# iobuf.net
KiCad netlist of a schematic drawn in EAGLE
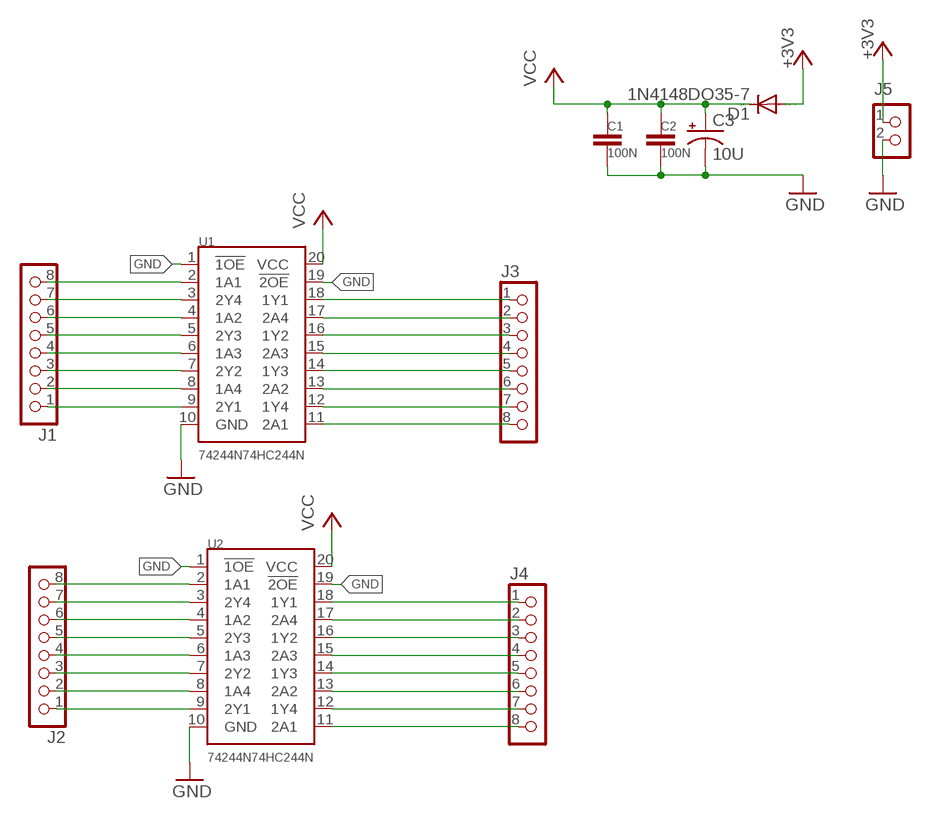
[diagram p0: schematic, sheet 1]

(export (version "E")
  (design (tool "Eeschema 10.0.6"))
  (components
    (comp (ref "C1")
      (value "100N")
      (footprint "eagle-import:C025-025X050")
      (libsource (lib "eagle-import") (part "C-EU025-025X050"))
    )
    (comp (ref "C2")
      (value "100N")
      (footprint "eagle-import:C025-025X050")
      (libsource (lib "eagle-import") (part "C-EU025-025X050"))
    )
    (comp (ref "C3")
      (value "10U")
      (footprint "eagle-import:E2,5-7")
      (libsource (lib "eagle-import") (part "CPOL-USE2.5-7"))
    )
    (comp (ref "D1")
      (value "1N4148DO35-7")
      (footprint "eagle-import:DO35-7")
      (libsource (lib "eagle-import") (part "1N4148DO35-7"))
    )
    (comp (ref "J1")
      (value "CON_HEADER_1X08-PTH")
      (footprint "eagle-import:M1X8")
      (libsource (lib "eagle-import") (part "CON_HEADER_1X08-PTH"))
    )
    (comp (ref "J2")
      (value "CON_HEADER_1X08-PTH")
      (footprint "eagle-import:M1X8")
      (libsource (lib "eagle-import") (part "CON_HEADER_1X08-PTH"))
    )
    (comp (ref "J3")
      (value "CON_HEADER_1X08-PTH")
      (footprint "eagle-import:M1X8")
      (libsource (lib "eagle-import") (part "CON_HEADER_1X08-PTH"))
    )
    (comp (ref "J4")
      (value "CON_HEADER_1X08-PTH")
      (footprint "eagle-import:M1X8")
      (libsource (lib "eagle-import") (part "CON_HEADER_1X08-PTH"))
    )
    (comp (ref "J5")
      (value "CON_HEADER_1X02-PTH")
      (footprint "eagle-import:M1X2")
      (libsource (lib "eagle-import") (part "CON_HEADER_1X02-PTH"))
    )
    (comp (ref "U1")
      (value "74244N74HC244N")
      (footprint "eagle-import:DIL20")
      (libsource (lib "eagle-import") (part "74244N74HC244N"))
    )
    (comp (ref "U2")
      (value "74244N74HC244N")
      (footprint "eagle-import:DIL20")
      (libsource (lib "eagle-import") (part "74244N74HC244N"))
    )
  )
  (nets
    (net (code "1") (name "+3V3") (class "Default")
      (node (ref "D1") (pin "A") (pinfunction "A_A") (pintype "passive"))
      (node (ref "J5") (pin "1") (pinfunction "1_1") (pintype "passive"))
    )
    (net (code "2") (name "GND") (class "Default")
      (node (ref "C1") (pin "2") (pinfunction "2_2") (pintype "passive"))
      (node (ref "C2") (pin "2") (pinfunction "2_2") (pintype "passive"))
      (node (ref "C3") (pin "-") (pinfunction "-_-") (pintype "passive"))
      (node (ref "J5") (pin "2") (pinfunction "2_2") (pintype "passive"))
      (node (ref "U1") (pin "1") (pinfunction "~{1OE}_1") (pintype "input"))
      (node (ref "U1") (pin "10") (pinfunction "GND_10") (pintype "power_in"))
      (node (ref "U1") (pin "19") (pinfunction "~{2OE}_19") (pintype "input"))
      (node (ref "U2") (pin "1") (pinfunction "~{1OE}_1") (pintype "input"))
      (node (ref "U2") (pin "10") (pinfunction "GND_10") (pintype "power_in"))
      (node (ref "U2") (pin "19") (pinfunction "~{2OE}_19") (pintype "input"))
    )
    (net (code "3") (name "Net-(U1-1A1)") (class "Default")
      (node (ref "J1") (pin "8") (pinfunction "8_8") (pintype "passive"))
      (node (ref "U1") (pin "2") (pinfunction "1A1_2") (pintype "bidirectional"))
    )
    (net (code "4") (name "Net-(U1-1A2)") (class "Default")
      (node (ref "J1") (pin "6") (pinfunction "6_6") (pintype "passive"))
      (node (ref "U1") (pin "4") (pinfunction "1A2_4") (pintype "bidirectional"))
    )
    (net (code "5") (name "Net-(U1-1A3)") (class "Default")
      (node (ref "J1") (pin "4") (pinfunction "4_4") (pintype "passive"))
      (node (ref "U1") (pin "6") (pinfunction "1A3_6") (pintype "bidirectional"))
    )
    (net (code "6") (name "Net-(U1-1A4)") (class "Default")
      (node (ref "J1") (pin "2") (pinfunction "2_2") (pintype "passive"))
      (node (ref "U1") (pin "8") (pinfunction "1A4_8") (pintype "bidirectional"))
    )
    (net (code "7") (name "Net-(U1-1Y1)") (class "Default")
      (node (ref "J3") (pin "1") (pinfunction "1_1") (pintype "passive"))
      (node (ref "U1") (pin "18") (pinfunction "1Y1_18") (pintype "bidirectional"))
    )
    (net (code "8") (name "Net-(U1-1Y2)") (class "Default")
      (node (ref "J3") (pin "3") (pinfunction "3_3") (pintype "passive"))
      (node (ref "U1") (pin "16") (pinfunction "1Y2_16") (pintype "bidirectional"))
    )
    (net (code "9") (name "Net-(U1-1Y3)") (class "Default")
      (node (ref "J3") (pin "5") (pinfunction "5_5") (pintype "passive"))
      (node (ref "U1") (pin "14") (pinfunction "1Y3_14") (pintype "bidirectional"))
    )
    (net (code "10") (name "Net-(U1-1Y4)") (class "Default")
      (node (ref "J3") (pin "7") (pinfunction "7_7") (pintype "passive"))
      (node (ref "U1") (pin "12") (pinfunction "1Y4_12") (pintype "bidirectional"))
    )
    (net (code "11") (name "Net-(U1-2A1)") (class "Default")
      (node (ref "J3") (pin "8") (pinfunction "8_8") (pintype "passive"))
      (node (ref "U1") (pin "11") (pinfunction "2A1_11") (pintype "bidirectional"))
    )
    (net (code "12") (name "Net-(U1-2A2)") (class "Default")
      (node (ref "J3") (pin "6") (pinfunction "6_6") (pintype "passive"))
      (node (ref "U1") (pin "13") (pinfunction "2A2_13") (pintype "bidirectional"))
    )
    (net (code "13") (name "Net-(U1-2A3)") (class "Default")
      (node (ref "J3") (pin "4") (pinfunction "4_4") (pintype "passive"))
      (node (ref "U1") (pin "15") (pinfunction "2A3_15") (pintype "bidirectional"))
    )
    (net (code "14") (name "Net-(U1-2A4)") (class "Default")
      (node (ref "J3") (pin "2") (pinfunction "2_2") (pintype "passive"))
      (node (ref "U1") (pin "17") (pinfunction "2A4_17") (pintype "bidirectional"))
    )
    (net (code "15") (name "Net-(U1-2Y1)") (class "Default")
      (node (ref "J1") (pin "1") (pinfunction "1_1") (pintype "passive"))
      (node (ref "U1") (pin "9") (pinfunction "2Y1_9") (pintype "bidirectional"))
    )
    (net (code "16") (name "Net-(U1-2Y2)") (class "Default")
      (node (ref "J1") (pin "3") (pinfunction "3_3") (pintype "passive"))
      (node (ref "U1") (pin "7") (pinfunction "2Y2_7") (pintype "bidirectional"))
    )
    (net (code "17") (name "Net-(U1-2Y3)") (class "Default")
      (node (ref "J1") (pin "5") (pinfunction "5_5") (pintype "passive"))
      (node (ref "U1") (pin "5") (pinfunction "2Y3_5") (pintype "bidirectional"))
    )
    (net (code "18") (name "Net-(U1-2Y4)") (class "Default")
      (node (ref "J1") (pin "7") (pinfunction "7_7") (pintype "passive"))
      (node (ref "U1") (pin "3") (pinfunction "2Y4_3") (pintype "bidirectional"))
    )
    (net (code "19") (name "Net-(U2-1A1)") (class "Default")
      (node (ref "J2") (pin "8") (pinfunction "8_8") (pintype "passive"))
      (node (ref "U2") (pin "2") (pinfunction "1A1_2") (pintype "bidirectional"))
    )
    (net (code "20") (name "Net-(U2-1A2)") (class "Default")
      (node (ref "J2") (pin "6") (pinfunction "6_6") (pintype "passive"))
      (node (ref "U2") (pin "4") (pinfunction "1A2_4") (pintype "bidirectional"))
    )
    (net (code "21") (name "Net-(U2-1A3)") (class "Default")
      (node (ref "J2") (pin "4") (pinfunction "4_4") (pintype "passive"))
      (node (ref "U2") (pin "6") (pinfunction "1A3_6") (pintype "bidirectional"))
    )
    (net (code "22") (name "Net-(U2-1A4)") (class "Default")
      (node (ref "J2") (pin "2") (pinfunction "2_2") (pintype "passive"))
      (node (ref "U2") (pin "8") (pinfunction "1A4_8") (pintype "bidirectional"))
    )
    (net (code "23") (name "Net-(U2-1Y1)") (class "Default")
      (node (ref "J4") (pin "1") (pinfunction "1_1") (pintype "passive"))
      (node (ref "U2") (pin "18") (pinfunction "1Y1_18") (pintype "bidirectional"))
    )
    (net (code "24") (name "Net-(U2-1Y2)") (class "Default")
      (node (ref "J4") (pin "3") (pinfunction "3_3") (pintype "passive"))
      (node (ref "U2") (pin "16") (pinfunction "1Y2_16") (pintype "bidirectional"))
    )
    (net (code "25") (name "Net-(U2-1Y3)") (class "Default")
      (node (ref "J4") (pin "5") (pinfunction "5_5") (pintype "passive"))
      (node (ref "U2") (pin "14") (pinfunction "1Y3_14") (pintype "bidirectional"))
    )
    (net (code "26") (name "Net-(U2-1Y4)") (class "Default")
      (node (ref "J4") (pin "7") (pinfunction "7_7") (pintype "passive"))
      (node (ref "U2") (pin "12") (pinfunction "1Y4_12") (pintype "bidirectional"))
    )
    (net (code "27") (name "Net-(U2-2A1)") (class "Default")
      (node (ref "J4") (pin "8") (pinfunction "8_8") (pintype "passive"))
      (node (ref "U2") (pin "11") (pinfunction "2A1_11") (pintype "bidirectional"))
    )
    (net (code "28") (name "Net-(U2-2A2)") (class "Default")
      (node (ref "J4") (pin "6") (pinfunction "6_6") (pintype "passive"))
      (node (ref "U2") (pin "13") (pinfunction "2A2_13") (pintype "bidirectional"))
    )
    (net (code "29") (name "Net-(U2-2A3)") (class "Default")
      (node (ref "J4") (pin "4") (pinfunction "4_4") (pintype "passive"))
      (node (ref "U2") (pin "15") (pinfunction "2A3_15") (pintype "bidirectional"))
    )
    (net (code "30") (name "Net-(U2-2A4)") (class "Default")
      (node (ref "J4") (pin "2") (pinfunction "2_2") (pintype "passive"))
      (node (ref "U2") (pin "17") (pinfunction "2A4_17") (pintype "bidirectional"))
    )
    (net (code "31") (name "Net-(U2-2Y1)") (class "Default")
      (node (ref "J2") (pin "1") (pinfunction "1_1") (pintype "passive"))
      (node (ref "U2") (pin "9") (pinfunction "2Y1_9") (pintype "bidirectional"))
    )
    (net (code "32") (name "Net-(U2-2Y2)") (class "Default")
      (node (ref "J2") (pin "3") (pinfunction "3_3") (pintype "passive"))
      (node (ref "U2") (pin "7") (pinfunction "2Y2_7") (pintype "bidirectional"))
    )
    (net (code "33") (name "Net-(U2-2Y3)") (class "Default")
      (node (ref "J2") (pin "5") (pinfunction "5_5") (pintype "passive"))
      (node (ref "U2") (pin "5") (pinfunction "2Y3_5") (pintype "bidirectional"))
    )
    (net (code "34") (name "Net-(U2-2Y4)") (class "Default")
      (node (ref "J2") (pin "7") (pinfunction "7_7") (pintype "passive"))
      (node (ref "U2") (pin "3") (pinfunction "2Y4_3") (pintype "bidirectional"))
    )
    (net (code "35") (name "VCC") (class "Default")
      (node (ref "C1") (pin "1") (pinfunction "1_1") (pintype "passive"))
      (node (ref "C2") (pin "1") (pinfunction "1_1") (pintype "passive"))
      (node (ref "C3") (pin "+") (pinfunction "+_+") (pintype "passive"))
      (node (ref "D1") (pin "C") (pinfunction "C_C") (pintype "passive"))
      (node (ref "U1") (pin "20") (pinfunction "VCC_20") (pintype "power_in"))
      (node (ref "U2") (pin "20") (pinfunction "VCC_20") (pintype "power_in"))
    )
  )
)
